# power.net
KiCad netlist of a schematic drawn in Altium Designer
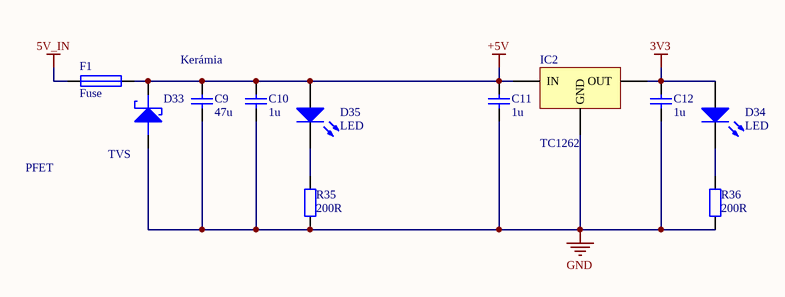
[diagram p0: power.SchDoc]

(export (version "E")
  (design (tool "Eeschema 10.0.6"))
  (components
    (comp (ref "C9")
      (value "47u")
      (footprint "FP_0805_CAP_085")
      (description "Capacitor")
      (libsource (lib "hallglib") (part "CAP"))
    )
    (comp (ref "C10")
      (value "1u")
      (footprint "FP_0805_CAP_085")
      (description "Capacitor")
      (libsource (lib "hallglib") (part "CAP"))
    )
    (comp (ref "C11")
      (value "1u")
      (footprint "FP_0805_CAP_085")
      (description "Capacitor")
      (libsource (lib "hallglib") (part "CAP"))
    )
    (comp (ref "C12")
      (value "1u")
      (footprint "FP_0805_CAP_085")
      (description "Capacitor")
      (libsource (lib "hallglib") (part "CAP"))
    )
    (comp (ref "D33")
      (value "TVS")
      (footprint "FP_SMB")
      (description "TVS diode")
      (libsource (lib "hallglib") (part "SCHOTTKY"))
    )
    (comp (ref "D34")
      (value "LED")
      (footprint "FP_0805_LED_GREEN")
      (description "Typical RED GaAs LED")
      (libsource (lib "hallglib") (part "LED"))
    )
    (comp (ref "D35")
      (value "LED")
      (footprint "FP_0805_LED_GREEN")
      (description "Typical RED GaAs LED")
      (libsource (lib "hallglib") (part "LED"))
    )
    (comp (ref "F1") (value "Fuse") (footprint "FP_MULTIFUSE") (libsource (lib "hallglib") (part "Fuse")))
    (comp (ref "IC2")
      (value "TC1262")
      (footprint "FP_SOT223")
      (description "Fixed LDO Voltage Regulator")
      (libsource (lib "mb") (part "TC1262"))
    )
    (comp (ref "R35")
      (value "200R")
      (footprint "FP_0805_RES")
      (description "Resistor")
      (libsource (lib "hallglib") (part "RES"))
    )
    (comp (ref "R36")
      (value "200R")
      (footprint "FP_0805_RES")
      (description "Resistor")
      (libsource (lib "hallglib") (part "RES"))
    )
  )
  (nets
    (net (code "1") (name "+5V") (class "Default")
      (node (ref "C10") (pin "2") (pinfunction "2_2") (pintype "passive"))
      (node (ref "C11") (pin "2") (pinfunction "2_2") (pintype "passive"))
      (node (ref "C9") (pin "2") (pinfunction "2_2") (pintype "passive"))
      (node (ref "D33") (pin "1") (pinfunction "CATHODE_1") (pintype "passive"))
      (node (ref "D35") (pin "1") (pinfunction "A_1") (pintype "passive"))
      (node (ref "F1") (pin "2") (pinfunction "2_2") (pintype "passive"))
      (node (ref "IC2") (pin "1") (pinfunction "IN_1") (pintype "passive"))
    )
    (net (code "2") (name "3V3") (class "Default")
      (node (ref "C12") (pin "2") (pinfunction "2_2") (pintype "passive"))
      (node (ref "D34") (pin "1") (pinfunction "A_1") (pintype "passive"))
      (node (ref "IC2") (pin "3") (pinfunction "OUT_3") (pintype "passive"))
    )
    (net (code "3") (name "5V_IN") (class "Default")
      (node (ref "F1") (pin "1") (pinfunction "1_1") (pintype "passive"))
    )
    (net (code "4") (name "GND") (class "Default")
      (node (ref "C10") (pin "1") (pinfunction "1_1") (pintype "passive"))
      (node (ref "C11") (pin "1") (pinfunction "1_1") (pintype "passive"))
      (node (ref "C12") (pin "1") (pinfunction "1_1") (pintype "passive"))
      (node (ref "C9") (pin "1") (pinfunction "1_1") (pintype "passive"))
      (node (ref "D33") (pin "2") (pinfunction "ANODE_2") (pintype "passive"))
      (node (ref "IC2") (pin "2") (pinfunction "GND_2") (pintype "passive"))
      (node (ref "R35") (pin "1") (pinfunction "1_1") (pintype "passive"))
      (node (ref "R36") (pin "1") (pinfunction "1_1") (pintype "passive"))
    )
    (net (code "5") (name "Net-(D34-K)") (class "Default")
      (node (ref "D34") (pin "2") (pinfunction "K_2") (pintype "passive"))
      (node (ref "R36") (pin "2") (pinfunction "2_2") (pintype "passive"))
    )
    (net (code "6") (name "Net-(D35-K)") (class "Default")
      (node (ref "D35") (pin "2") (pinfunction "K_2") (pintype "passive"))
      (node (ref "R35") (pin "2") (pinfunction "2_2") (pintype "passive"))
    )
  )
)
